# ProDoc_P1_2024-06-28.net
KiCad netlist of a schematic drawn in EasyEDA Pro
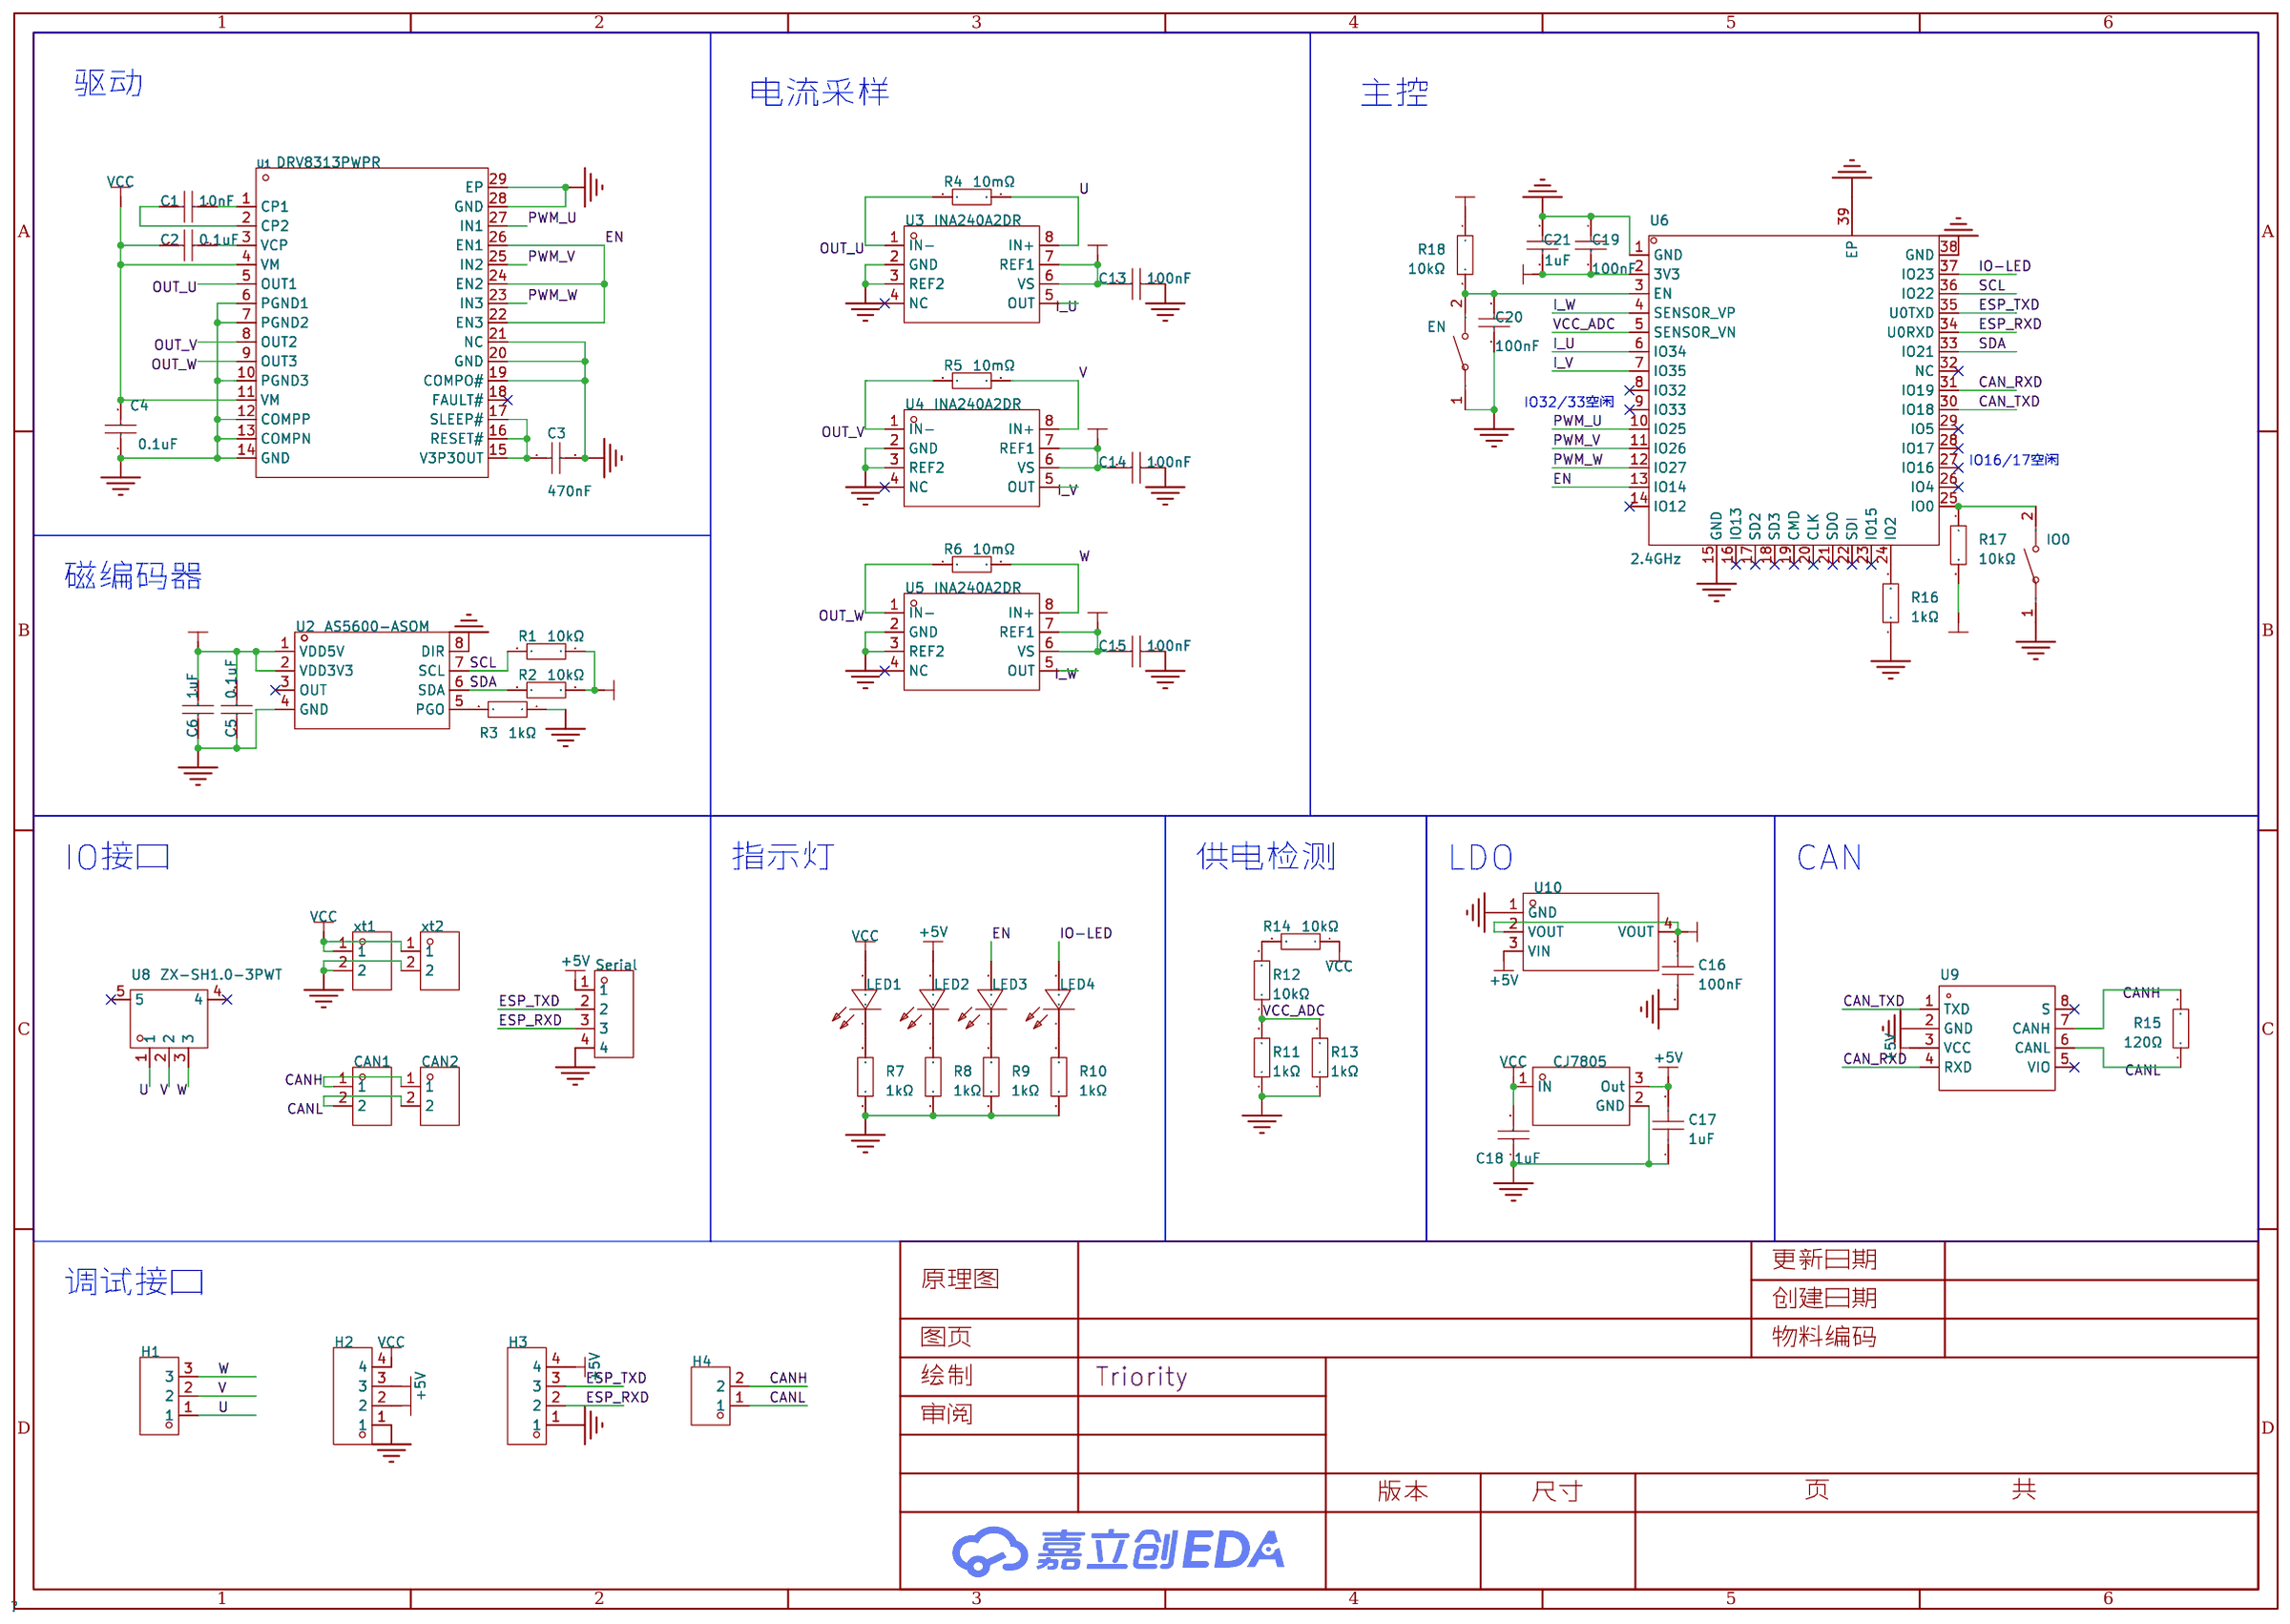
[diagram p0: schematic sheet]

(export (version "E")
  (design (tool "Eeschema 10.0.6"))
  (components
    (comp (ref "C1")
      (value "10nF")
      (footprint "easyedapro:C0603")
      (description "容值:10nF;精度:±10%;额定电压:50V;材质(温度系数):X7R;")
      (fields
        (field (name "Manufacturer Part") "CC0603KRX7R9BB103")
        (field (name "Manufacturer") "YAGEO(国巨)")
      )
      (libsource (lib "easyedapro") (part "CC0603KRX7R9BB103"))
    )
    (comp (ref "C2")
      (value "0.1uF")
      (footprint "easyedapro:C0603")
      (description "容值:100nF;精度:±10%;额定电压:50V;材质(温度系数):X7R;")
      (fields (field (name "Manufacturer Part") "0603B104K500NT") (field (name "Manufacturer") "FH(风华)"))
      (libsource (lib "easyedapro") (part "0603B104K500NT"))
    )
    (comp (ref "C3")
      (value "470nF")
      (footprint "easyedapro:C0603")
      (description "容值:470nF;精度:±10%;额定电压:25V;材质(温度系数):X7R;")
      (fields
        (field (name "Manufacturer Part") "CL10B474KA8NNNC")
        (field (name "Manufacturer") "SAMSUNG(三星)")
      )
      (libsource (lib "easyedapro") (part "CL10B474KA8NNNC"))
    )
    (comp (ref "C4")
      (value "0.1uF")
      (footprint "easyedapro:C0603")
      (description "容值:100nF;精度:±10%;额定电压:50V;材质(温度系数):X7R;")
      (fields (field (name "Manufacturer Part") "0603B104K500NT") (field (name "Manufacturer") "FH(风华)"))
      (libsource (lib "easyedapro") (part "0603B104K500NT"))
    )
    (comp (ref "C5")
      (value "0.1uF")
      (footprint "easyedapro:C0603")
      (description "容值:100nF;精度:±10%;额定电压:50V;材质(温度系数):X7R;")
      (fields (field (name "Manufacturer Part") "0603B104K500NT") (field (name "Manufacturer") "FH(风华)"))
      (libsource (lib "easyedapro") (part "0603B104K500NT"))
    )
    (comp (ref "C6")
      (value "1uF")
      (footprint "easyedapro:C0603")
      (description "容值:1uF;精度:±10%;额定电压:50V;材质(温度系数):X5R;")
      (fields
        (field (name "Manufacturer Part") "CL10A105KB8NNNC")
        (field (name "Manufacturer") "SAMSUNG(三星)")
      )
      (libsource (lib "easyedapro") (part "CL10A105KB8NNNC"))
    )
    (comp (ref "C13")
      (value "100nF")
      (footprint "easyedapro:C0603")
      (description "容值:100nF;精度:±10%;额定电压:50V;材质(温度系数):X7R;")
      (fields (field (name "Manufacturer Part") "0603B104K500NT") (field (name "Manufacturer") "FH(风华)"))
      (libsource (lib "easyedapro") (part "0603B104K500NT"))
    )
    (comp (ref "C14")
      (value "100nF")
      (footprint "easyedapro:C0603")
      (description "容值:100nF;精度:±10%;额定电压:50V;材质(温度系数):X7R;")
      (fields (field (name "Manufacturer Part") "0603B104K500NT") (field (name "Manufacturer") "FH(风华)"))
      (libsource (lib "easyedapro") (part "0603B104K500NT"))
    )
    (comp (ref "C15")
      (value "100nF")
      (footprint "easyedapro:C0603")
      (description "容值:100nF;精度:±10%;额定电压:50V;材质(温度系数):X7R;")
      (fields (field (name "Manufacturer Part") "0603B104K500NT") (field (name "Manufacturer") "FH(风华)"))
      (libsource (lib "easyedapro") (part "0603B104K500NT"))
    )
    (comp (ref "C16")
      (value "100nF")
      (footprint "easyedapro:C0603")
      (description "容值:100nF;精度:±10%;额定电压:50V;材质(温度系数):X7R;")
      (fields
        (field (name "Manufacturer Part") "CC0603KRX7R9BB104")
        (field (name "Manufacturer") "YAGEO(国巨)")
      )
      (libsource (lib "easyedapro") (part "CC0603KRX7R9BB104"))
    )
    (comp (ref "C17")
      (value "1uF")
      (footprint "easyedapro:C0603")
      (description "容值:100nF;精度:±10%;额定电压:50V;材质(温度系数):X7R;")
      (fields
        (field (name "Manufacturer Part") "CC0603KRX7R9BB104")
        (field (name "Manufacturer") "YAGEO(国巨)")
      )
      (libsource (lib "easyedapro") (part "CC0603KRX7R9BB104"))
    )
    (comp (ref "C18")
      (value "1uF")
      (footprint "easyedapro:C0603")
      (description "容值:1uF;精度:±10%;额定电压:50V;材质(温度系数):X5R;")
      (fields
        (field (name "Manufacturer Part") "CL10A105KB8NNNC")
        (field (name "Manufacturer") "SAMSUNG(三星)")
      )
      (libsource (lib "easyedapro") (part "CL10A105KB8NNNC"))
    )
    (comp (ref "C19")
      (value "100nF")
      (footprint "easyedapro:C0603")
      (description "容值:100nF;精度:±10%;额定电压:50V;材质(温度系数):X7R;")
      (fields (field (name "Manufacturer Part") "0603B104K500NT") (field (name "Manufacturer") "FH(风华)"))
      (libsource (lib "easyedapro") (part "0603B104K500NT"))
    )
    (comp (ref "C20")
      (value "100nF")
      (footprint "easyedapro:C0603")
      (description "容值:100nF;精度:±10%;额定电压:50V;材质(温度系数):X7R;")
      (fields (field (name "Manufacturer Part") "0603B104K500NT") (field (name "Manufacturer") "FH(风华)"))
      (libsource (lib "easyedapro") (part "0603B104K500NT"))
    )
    (comp (ref "C21")
      (value "1uF")
      (footprint "easyedapro:C0603")
      (description "容值:1uF;精度:±10%;额定电压:50V;材质(温度系数):X5R;")
      (fields
        (field (name "Manufacturer Part") "CL10A105KB8NNNC")
        (field (name "Manufacturer") "SAMSUNG(三星)")
      )
      (libsource (lib "easyedapro") (part "CL10A105KB8NNNC"))
    )
    (comp (ref "CAN1")
      (value "XH-2AW")
      (footprint "easyedapro:CONN-TH_XH-2AW_C2908611")
      (fields (field (name "Manufacturer") "HCTL(华灿天禄)"))
      (libsource (lib "easyedapro") (part "XH-2AW_C2908611"))
    )
    (comp (ref "CAN2")
      (value "XH-2AW")
      (footprint "easyedapro:CONN-TH_XH-2AW_C2908611")
      (fields (field (name "Manufacturer") "HCTL(华灿天禄)"))
      (libsource (lib "easyedapro") (part "XH-2AW_C2908611"))
    )
    (comp (ref "CJ7805")
      (value "CJ7805 3%")
      (footprint "easyedapro:TO-252-2_L6.6-W6.1-P4.58-LS10.1-BR-CW")
      (description "输出类型:固定;最大输入电压:35V;输出电压:5V;最大输出电流:1.5A;输出极性:正极;")
      (fields (field (name "Manufacturer") "CJ(江苏长电/长晶)"))
      (libsource (lib "easyedapro") (part "CJ7805 3%"))
    )
    (comp (ref "EN")
      (value "K2-1107ST-A4DW-06")
      (footprint "easyedapro:KEY-SMD_L6.2-W3.6-LS8.0")
      (fields (field (name "Manufacturer") "韩国韩荣"))
      (libsource (lib "easyedapro") (part "K2-1107ST-A4SW-06"))
    )
    (comp (ref "H1")
      (value "PZ254V-11-03P")
      (footprint "easyedapro:HDR-TH_3P-P2.54-V-M")
      (fields (field (name "Manufacturer") "XFCN(兴飞)"))
      (libsource (lib "easyedapro") (part "PZ254V-11-03P_C2937625"))
    )
    (comp (ref "H2")
      (value "PZ254V-11-04P")
      (footprint "easyedapro:HDR-TH_4P-P2.54-V-M")
      (fields (field (name "Manufacturer") "XFCN(兴飞)"))
      (libsource (lib "easyedapro") (part "PZ254V-11-04P_C2691448"))
    )
    (comp (ref "H3")
      (value "PZ254V-11-04P")
      (footprint "easyedapro:HDR-TH_4P-P2.54-V-M")
      (fields (field (name "Manufacturer") "XFCN(兴飞)"))
      (libsource (lib "easyedapro") (part "PZ254V-11-04P_C2691448"))
    )
    (comp (ref "H4")
      (value "PZ254V-11-02P")
      (footprint "easyedapro:HDR-TH_2P-P2.54-V-M")
      (fields (field (name "Manufacturer") "XFCN(兴飞)"))
      (libsource (lib "easyedapro") (part "PZ254V-11-02P"))
    )
    (comp (ref "IO0")
      (value "K2-1107ST-A4DW-06")
      (footprint "easyedapro:KEY-SMD_L6.2-W3.6-LS8.0")
      (fields (field (name "Manufacturer") "韩国韩荣"))
      (libsource (lib "easyedapro") (part "K2-1107ST-A4SW-06"))
    )
    (comp (ref "LED1")
      (value "KT-0603R")
      (footprint "easyedapro:LED0603-RD")
      (description "发光颜色:红色;功率:-;正向电流:-;主波长:-;二极管配置:-;透镜颜色:-;色温:-;发光角度:-;载带方式:-;工作温度:-40°C~+85°C;")
      (fields (field (name "Manufacturer") "KENTO"))
      (libsource (lib "easyedapro") (part "KT-0603R"))
    )
    (comp (ref "LED2")
      (value "KT-0603R")
      (footprint "easyedapro:LED0603-RD")
      (description "发光颜色:红色;功率:-;正向电流:-;主波长:-;二极管配置:-;透镜颜色:-;色温:-;发光角度:-;载带方式:-;工作温度:-40°C~+85°C;")
      (fields (field (name "Manufacturer") "KENTO"))
      (libsource (lib "easyedapro") (part "KT-0603R"))
    )
    (comp (ref "LED3")
      (value "KT-0603R")
      (footprint "easyedapro:LED0603-RD")
      (description "发光颜色:红色;功率:-;正向电流:-;主波长:-;二极管配置:-;透镜颜色:-;色温:-;发光角度:-;载带方式:-;工作温度:-40°C~+85°C;")
      (fields (field (name "Manufacturer") "KENTO"))
      (libsource (lib "easyedapro") (part "KT-0603R"))
    )
    (comp (ref "LED4")
      (value "KT-0603R")
      (footprint "easyedapro:LED0603-RD")
      (description "发光颜色:红色;功率:-;正向电流:-;主波长:-;二极管配置:-;透镜颜色:-;色温:-;发光角度:-;载带方式:-;工作温度:-40°C~+85°C;")
      (fields (field (name "Manufacturer") "KENTO"))
      (libsource (lib "easyedapro") (part "KT-0603R"))
    )
    (comp (ref "R1")
      (value "10kΩ")
      (footprint "easyedapro:R0603")
      (description "电阻类型:厚膜电阻;阻值:10kΩ;精度:±1%;功率:100mW;最大工作电压:75V;温度系数:±100ppm/°C;")
      (fields (field (name "Manufacturer Part") "RC0603FR-0710KL") (field (name "Manufacturer") "YAGEO(国巨)"))
      (libsource (lib "easyedapro") (part "RC0603FR-0710KL"))
    )
    (comp (ref "R2")
      (value "10kΩ")
      (footprint "easyedapro:R0603")
      (description "电阻类型:厚膜电阻;阻值:10kΩ;精度:±1%;功率:100mW;最大工作电压:75V;温度系数:±100ppm/°C;")
      (fields (field (name "Manufacturer Part") "RC0603FR-0710KL") (field (name "Manufacturer") "YAGEO(国巨)"))
      (libsource (lib "easyedapro") (part "RC0603FR-0710KL"))
    )
    (comp (ref "R3")
      (value "1kΩ")
      (footprint "easyedapro:R0603")
      (description "电阻类型:厚膜电阻;阻值:1kΩ;精度:±1%;功率:100mW;最大工作电压:75V;温度系数:±100ppm/°C;")
      (fields (field (name "Manufacturer Part") "RC0603FR-071KL") (field (name "Manufacturer") "YAGEO(国巨)"))
      (libsource (lib "easyedapro") (part "RC0603FR-071KL"))
    )
    (comp (ref "R4")
      (value "10mΩ")
      (footprint "easyedapro:R1206")
      (description "阻值:10mΩ;精度:±1%;功率:1W;温度系数:±100ppm/°C;")
      (fields (field (name "Manufacturer Part") "RLM12FTCMR010") (field (name "Manufacturer") "大毅科技"))
      (libsource (lib "easyedapro") (part "RLM12FTCMR010"))
    )
    (comp (ref "R5")
      (value "10mΩ")
      (footprint "easyedapro:R1206")
      (description "阻值:10mΩ;精度:±1%;功率:1W;温度系数:±100ppm/°C;")
      (fields (field (name "Manufacturer Part") "RLM12FTCMR010") (field (name "Manufacturer") "大毅科技"))
      (libsource (lib "easyedapro") (part "RLM12FTCMR010"))
    )
    (comp (ref "R6")
      (value "10mΩ")
      (footprint "easyedapro:R1206")
      (description "阻值:10mΩ;精度:±1%;功率:1W;温度系数:±100ppm/°C;")
      (fields (field (name "Manufacturer Part") "RLM12FTCMR010") (field (name "Manufacturer") "大毅科技"))
      (libsource (lib "easyedapro") (part "RLM12FTCMR010"))
    )
    (comp (ref "R7")
      (value "1kΩ")
      (footprint "easyedapro:R0603")
      (description "电阻类型:厚膜电阻;阻值:1kΩ;精度:±1%;功率:100mW;最大工作电压:75V;温度系数:±100ppm/°C;")
      (fields
        (field (name "Manufacturer Part") "0603WAF1001T5E")
        (field (name "Manufacturer") "UNI-ROYAL(厚声)")
      )
      (libsource (lib "easyedapro") (part "0603WAF1001T5E"))
    )
    (comp (ref "R8")
      (value "1kΩ")
      (footprint "easyedapro:R0603")
      (description "电阻类型:厚膜电阻;阻值:1kΩ;精度:±1%;功率:100mW;最大工作电压:75V;温度系数:±100ppm/°C;")
      (fields
        (field (name "Manufacturer Part") "0603WAF1001T5E")
        (field (name "Manufacturer") "UNI-ROYAL(厚声)")
      )
      (libsource (lib "easyedapro") (part "0603WAF1001T5E"))
    )
    (comp (ref "R9")
      (value "1kΩ")
      (footprint "easyedapro:R0603")
      (description "电阻类型:厚膜电阻;阻值:1kΩ;精度:±1%;功率:100mW;最大工作电压:75V;温度系数:±100ppm/°C;")
      (fields
        (field (name "Manufacturer Part") "0603WAF1001T5E")
        (field (name "Manufacturer") "UNI-ROYAL(厚声)")
      )
      (libsource (lib "easyedapro") (part "0603WAF1001T5E"))
    )
    (comp (ref "R10")
      (value "1kΩ")
      (footprint "easyedapro:R0603")
      (description "电阻类型:厚膜电阻;阻值:1kΩ;精度:±1%;功率:100mW;最大工作电压:75V;温度系数:±100ppm/°C;")
      (fields
        (field (name "Manufacturer Part") "0603WAF1001T5E")
        (field (name "Manufacturer") "UNI-ROYAL(厚声)")
      )
      (libsource (lib "easyedapro") (part "0603WAF1001T5E"))
    )
    (comp (ref "R11")
      (value "1kΩ")
      (footprint "easyedapro:R0603")
      (description "电阻类型:厚膜电阻;阻值:1kΩ;精度:±1%;功率:100mW;最大工作电压:75V;温度系数:±100ppm/°C;")
      (fields
        (field (name "Manufacturer Part") "0603WAF1001T5E")
        (field (name "Manufacturer") "UNI-ROYAL(厚声)")
      )
      (libsource (lib "easyedapro") (part "0603WAF1001T5E"))
    )
    (comp (ref "R12")
      (value "10kΩ")
      (footprint "easyedapro:R0603")
      (description "电阻类型:厚膜电阻;阻值:10kΩ;精度:±1%;功率:100mW;最大工作电压:75V;温度系数:±100ppm/°C;")
      (fields (field (name "Manufacturer Part") "RC0603FR-0710KL") (field (name "Manufacturer") "YAGEO(国巨)"))
      (libsource (lib "easyedapro") (part "RC0603FR-0710KL"))
    )
    (comp (ref "R13")
      (value "1kΩ")
      (footprint "easyedapro:R0603")
      (description "电阻类型:厚膜电阻;阻值:1kΩ;精度:±1%;功率:100mW;最大工作电压:75V;温度系数:±100ppm/°C;")
      (fields
        (field (name "Manufacturer Part") "0603WAF1001T5E")
        (field (name "Manufacturer") "UNI-ROYAL(厚声)")
      )
      (libsource (lib "easyedapro") (part "0603WAF1001T5E"))
    )
    (comp (ref "R14")
      (value "10kΩ")
      (footprint "easyedapro:R0603")
      (description "电阻类型:厚膜电阻;阻值:10kΩ;精度:±1%;功率:100mW;最大工作电压:75V;温度系数:±100ppm/°C;")
      (fields (field (name "Manufacturer Part") "RC0603FR-0710KL") (field (name "Manufacturer") "YAGEO(国巨)"))
      (libsource (lib "easyedapro") (part "RC0603FR-0710KL"))
    )
    (comp (ref "R15")
      (value "120Ω")
      (footprint "easyedapro:R0603")
      (description "电阻类型:厚膜电阻;阻值:120Ω;精度:±1%;功率:100mW;最大工作电压:75V;温度系数:±100ppm/°C;")
      (fields
        (field (name "Manufacturer Part") "0603WAF1200T5E")
        (field (name "Manufacturer") "UNI-ROYAL(厚声)")
      )
      (libsource (lib "easyedapro") (part "0603WAF1200T5E"))
    )
    (comp (ref "R16")
      (value "1kΩ")
      (footprint "easyedapro:R0603")
      (description "电阻类型:厚膜电阻;阻值:1kΩ;精度:±1%;功率:100mW;最大工作电压:75V;温度系数:±100ppm/°C;")
      (fields
        (field (name "Manufacturer Part") "0603WAF1001T5E")
        (field (name "Manufacturer") "UNI-ROYAL(厚声)")
      )
      (libsource (lib "easyedapro") (part "0603WAF1001T5E"))
    )
    (comp (ref "R17")
      (value "10kΩ")
      (footprint "easyedapro:R0603")
      (description "电阻类型:厚膜电阻;阻值:10kΩ;精度:±1%;功率:100mW;最大工作电压:75V;温度系数:±100ppm/°C;")
      (fields (field (name "Manufacturer Part") "RC0603FR-0710KL") (field (name "Manufacturer") "YAGEO(国巨)"))
      (libsource (lib "easyedapro") (part "RC0603FR-0710KL"))
    )
    (comp (ref "R18")
      (value "10kΩ")
      (footprint "easyedapro:R0603")
      (description "电阻类型:厚膜电阻;阻值:10kΩ;精度:±1%;功率:100mW;最大工作电压:75V;温度系数:±100ppm/°C;")
      (fields (field (name "Manufacturer Part") "RC0603FR-0710KL") (field (name "Manufacturer") "YAGEO(国巨)"))
      (libsource (lib "easyedapro") (part "RC0603FR-0710KL"))
    )
    (comp (ref "Serial")
      (value "XH-4AW")
      (footprint "easyedapro:CONN-TH_XH-4AW")
      (fields (field (name "Manufacturer") "HCTL(华灿天禄)"))
      (libsource (lib "easyedapro") (part "XH-4AW_C2908613"))
    )
    (comp (ref "U1")
      (value "DRV8313PWPR")
      (footprint "easyedapro:HTSSOP-28_L9.8-W4.5-P0.65-LS6.6-BL-EP")
      (description "驱动电机类型:无刷直流BLDC;电源电压:8V~60V;输出电流:-;接口:并行;")
      (fields (field (name "Manufacturer") "TI(德州仪器)"))
      (libsource (lib "easyedapro") (part "DRV8313PWPR"))
    )
    (comp (ref "U2")
      (value "AS5600-ASOM")
      (footprint "easyedapro:SOIC-8_L5.0-W4.0-P1.27-LS6.0-BL")
      (description "旋转角度范围:0°~360°;")
      (fields (field (name "Manufacturer") "ams(艾迈斯半导体)"))
      (libsource (lib "easyedapro") (part "AS5600-ASOM"))
    )
    (comp (ref "U3")
      (value "INA240A2DR")
      (footprint "easyedapro:SOIC-8_L4.9-W3.9-P1.27-LS6.0-BL")
      (description "放大器数:单路;")
      (fields (field (name "Manufacturer") "TI(德州仪器)"))
      (libsource (lib "easyedapro") (part "INA240A2DR"))
    )
    (comp (ref "U4")
      (value "INA240A2DR")
      (footprint "easyedapro:SOIC-8_L4.9-W3.9-P1.27-LS6.0-BL")
      (description "放大器数:单路;")
      (fields (field (name "Manufacturer") "TI(德州仪器)"))
      (libsource (lib "easyedapro") (part "INA240A2DR"))
    )
    (comp (ref "U5")
      (value "INA240A2DR")
      (footprint "easyedapro:SOIC-8_L4.9-W3.9-P1.27-LS6.0-BL")
      (description "放大器数:单路;")
      (fields (field (name "Manufacturer") "TI(德州仪器)"))
      (libsource (lib "easyedapro") (part "INA240A2DR"))
    )
    (comp (ref "U6")
      (value "2.4GHz")
      (footprint "easyedapro:WIRELM-SMD_ESP32-S")
      (description "核心处理器:ESP32芯片;频率:2.4GHz;天线形式:IPEX接口;发射功率:17dBm;接收灵敏度:-90dBm;")
      (fields (field (name "Manufacturer Part") "ESP32-S") (field (name "Manufacturer") "Ai-Thinker(安信可)"))
      (libsource (lib "easyedapro") (part "ESP32-S"))
    )
    (comp (ref "U8")
      (value "ZX-SH1.0-3PWT")
      (footprint "easyedapro:CONN-SMD_3P-P1.00_MEGASTAR_ZX-SH1.0-3PWT")
      (fields (field (name "Manufacturer") "Megastar(兆星)"))
      (libsource (lib "easyedapro") (part "ZX-SH1.0-3PWT"))
    )
    (comp (ref "U9")
      (value "TJA1051T/3/1J")
      (footprint "easyedapro:SOIC-8_L4.9-W3.9-P1.27-LS6.0-BL")
      (description "类型:收发器;数据速率:5Mbps;")
      (fields (field (name "Manufacturer") "NXP(恩智浦)"))
      (libsource (lib "easyedapro") (part "TJA1051T/3/1J"))
    )
    (comp (ref "U10")
      (value "AMS1117-3.3")
      (footprint "easyedapro:SOT-223-3_L6.5-W3.4-P2.30-LS7.0-BR")
      (description "输出类型:固定;最大输入电压:-;输出电压:3.3V;最大输出电流:1A;电源纹波抑制比(PSRR):72dB@(120Hz);输出极性:正极;")
      (fields (field (name "Manufacturer") "AMS"))
      (libsource (lib "easyedapro") (part "AMS1117-3.3"))
    )
    (comp (ref "xt1")
      (value "XT30U-M")
      (footprint "easyedapro:CONN-TH_XT30U-M")
      (description "类别:-;类型1:-;")
      (fields (field (name "Manufacturer") "AMASS(艾迈斯)"))
      (libsource (lib "easyedapro") (part "XT30U-M"))
    )
    (comp (ref "xt2")
      (value "XT30U-M")
      (footprint "easyedapro:CONN-TH_XT30U-M")
      (description "类别:-;类型1:-;")
      (fields (field (name "Manufacturer") "AMASS(艾迈斯)"))
      (libsource (lib "easyedapro") (part "XT30U-M"))
    )
  )
  (nets
    (net (code "1") (name "+5V") (class "Default")
      (node (ref "C17") (pin "2") (pinfunction "2_2") (pintype "unspecified"))
      (node (ref "CJ7805") (pin "3") (pinfunction "Out_3") (pintype "unspecified"))
      (node (ref "H2") (pin "3") (pinfunction "3_3") (pintype "unspecified"))
      (node (ref "H3") (pin "4") (pinfunction "4_4") (pintype "unspecified"))
      (node (ref "LED2") (pin "2") (pinfunction "A_2") (pintype "input"))
      (node (ref "Serial") (pin "1") (pinfunction "1_1") (pintype "unspecified"))
      (node (ref "U10") (pin "3") (pinfunction "VIN_3") (pintype "unspecified"))
      (node (ref "U9") (pin "3") (pinfunction "VCC_3") (pintype "input"))
    )
    (net (code "2") (name "/CANH") (class "Default")
      (node (ref "CAN1") (pin "1") (pinfunction "1_1") (pintype "unspecified"))
      (node (ref "CAN2") (pin "1") (pinfunction "1_1") (pintype "unspecified"))
      (node (ref "H4") (pin "2") (pinfunction "2_2") (pintype "unspecified"))
      (node (ref "R15") (pin "2") (pinfunction "2_2") (pintype "input"))
      (node (ref "U9") (pin "7") (pinfunction "CANH_7") (pintype "input"))
    )
    (net (code "3") (name "/CANL") (class "Default")
      (node (ref "CAN1") (pin "2") (pinfunction "2_2") (pintype "unspecified"))
      (node (ref "CAN2") (pin "2") (pinfunction "2_2") (pintype "unspecified"))
      (node (ref "H4") (pin "1") (pinfunction "1_1") (pintype "unspecified"))
      (node (ref "R15") (pin "1") (pinfunction "1_1") (pintype "input"))
      (node (ref "U9") (pin "6") (pinfunction "CANL_6") (pintype "input"))
    )
    (net (code "4") (name "/CAN_RXD") (class "Default")
      (node (ref "U6") (pin "31") (pinfunction "IO19_31") (pintype "input"))
      (node (ref "U9") (pin "4") (pinfunction "RXD_4") (pintype "input"))
    )
    (net (code "5") (name "/CAN_TXD") (class "Default")
      (node (ref "U6") (pin "30") (pinfunction "IO18_30") (pintype "input"))
      (node (ref "U9") (pin "1") (pinfunction "TXD_1") (pintype "input"))
    )
    (net (code "6") (name "/EN") (class "Default")
      (node (ref "LED3") (pin "2") (pinfunction "A_2") (pintype "input"))
      (node (ref "U1") (pin "22") (pinfunction "EN3_22") (pintype "input"))
      (node (ref "U1") (pin "24") (pinfunction "EN2_24") (pintype "input"))
      (node (ref "U1") (pin "26") (pinfunction "EN1_26") (pintype "input"))
      (node (ref "U6") (pin "13") (pinfunction "IO14_13") (pintype "input"))
    )
    (net (code "7") (name "/ESP_RXD") (class "Default")
      (node (ref "H3") (pin "2") (pinfunction "2_2") (pintype "unspecified"))
      (node (ref "Serial") (pin "3") (pinfunction "3_3") (pintype "unspecified"))
      (node (ref "U6") (pin "34") (pinfunction "U0RXD_34") (pintype "input"))
    )
    (net (code "8") (name "/ESP_TXD") (class "Default")
      (node (ref "H3") (pin "3") (pinfunction "3_3") (pintype "unspecified"))
      (node (ref "Serial") (pin "2") (pinfunction "2_2") (pintype "unspecified"))
      (node (ref "U6") (pin "35") (pinfunction "U0TXD_35") (pintype "input"))
    )
    (net (code "9") (name "/IO-LED") (class "Default")
      (node (ref "LED4") (pin "2") (pinfunction "A_2") (pintype "input"))
      (node (ref "U6") (pin "37") (pinfunction "IO23_37") (pintype "input"))
    )
    (net (code "10") (name "/I_U") (class "Default")
      (node (ref "U3") (pin "5") (pinfunction "OUT_5") (pintype "input"))
      (node (ref "U6") (pin "6") (pinfunction "IO34_6") (pintype "input"))
    )
    (net (code "11") (name "/I_V") (class "Default")
      (node (ref "U4") (pin "5") (pinfunction "OUT_5") (pintype "input"))
      (node (ref "U6") (pin "7") (pinfunction "IO35_7") (pintype "input"))
    )
    (net (code "12") (name "/I_W") (class "Default")
      (node (ref "U5") (pin "5") (pinfunction "OUT_5") (pintype "input"))
      (node (ref "U6") (pin "4") (pinfunction "SENSOR_VP_4") (pintype "input"))
    )
    (net (code "13") (name "/OUT_U") (class "Default")
      (node (ref "R4") (pin "1") (pinfunction "1_1") (pintype "input"))
      (node (ref "U1") (pin "5") (pinfunction "OUT1_5") (pintype "input"))
      (node (ref "U3") (pin "1") (pinfunction "IN-_1") (pintype "input"))
    )
    (net (code "14") (name "/OUT_V") (class "Default")
      (node (ref "R5") (pin "1") (pinfunction "1_1") (pintype "input"))
      (node (ref "U1") (pin "8") (pinfunction "OUT2_8") (pintype "input"))
      (node (ref "U4") (pin "1") (pinfunction "IN-_1") (pintype "input"))
    )
    (net (code "15") (name "/OUT_W") (class "Default")
      (node (ref "R6") (pin "1") (pinfunction "1_1") (pintype "input"))
      (node (ref "U1") (pin "9") (pinfunction "OUT3_9") (pintype "input"))
      (node (ref "U5") (pin "1") (pinfunction "IN-_1") (pintype "input"))
    )
    (net (code "16") (name "/PWM_U") (class "Default")
      (node (ref "U1") (pin "27") (pinfunction "IN1_27") (pintype "input"))
      (node (ref "U6") (pin "10") (pinfunction "IO25_10") (pintype "input"))
    )
    (net (code "17") (name "/PWM_V") (class "Default")
      (node (ref "U1") (pin "25") (pinfunction "IN2_25") (pintype "input"))
      (node (ref "U6") (pin "11") (pinfunction "IO26_11") (pintype "input"))
    )
    (net (code "18") (name "/PWM_W") (class "Default")
      (node (ref "U1") (pin "23") (pinfunction "IN3_23") (pintype "input"))
      (node (ref "U6") (pin "12") (pinfunction "IO27_12") (pintype "input"))
    )
    (net (code "19") (name "/SCL") (class "Default")
      (node (ref "R1") (pin "2") (pinfunction "2_2") (pintype "input"))
      (node (ref "U2") (pin "7") (pinfunction "SCL_7") (pintype "input"))
      (node (ref "U6") (pin "36") (pinfunction "IO22_36") (pintype "input"))
    )
    (net (code "20") (name "/SDA") (class "Default")
      (node (ref "R2") (pin "2") (pinfunction "2_2") (pintype "input"))
      (node (ref "U2") (pin "6") (pinfunction "SDA_6") (pintype "input"))
      (node (ref "U6") (pin "33") (pinfunction "IO21_33") (pintype "input"))
    )
    (net (code "21") (name "/U") (class "Default")
      (node (ref "H1") (pin "1") (pinfunction "1_1") (pintype "unspecified"))
      (node (ref "R4") (pin "2") (pinfunction "2_2") (pintype "input"))
      (node (ref "U3") (pin "8") (pinfunction "IN+_8") (pintype "input"))
      (node (ref "U8") (pin "1") (pinfunction "1_1") (pintype "unspecified"))
    )
    (net (code "22") (name "/V") (class "Default")
      (node (ref "H1") (pin "2") (pinfunction "2_2") (pintype "unspecified"))
      (node (ref "R5") (pin "2") (pinfunction "2_2") (pintype "input"))
      (node (ref "U4") (pin "8") (pinfunction "IN+_8") (pintype "input"))
      (node (ref "U8") (pin "2") (pinfunction "2_2") (pintype "unspecified"))
    )
    (net (code "23") (name "/VCC_ADC") (class "Default")
      (node (ref "R11") (pin "2") (pinfunction "2_2") (pintype "input"))
      (node (ref "R12") (pin "1") (pinfunction "1_1") (pintype "input"))
      (node (ref "R13") (pin "2") (pinfunction "2_2") (pintype "input"))
      (node (ref "U6") (pin "5") (pinfunction "SENSOR_VN_5") (pintype "input"))
    )
    (net (code "24") (name "/W") (class "Default")
      (node (ref "H1") (pin "3") (pinfunction "3_3") (pintype "unspecified"))
      (node (ref "R6") (pin "2") (pinfunction "2_2") (pintype "input"))
      (node (ref "U5") (pin "8") (pinfunction "IN+_8") (pintype "input"))
      (node (ref "U8") (pin "3") (pinfunction "3_3") (pintype "unspecified"))
    )
    (net (code "25") (name "3V3") (class "Default")
      (node (ref "C13") (pin "2") (pinfunction "2_2") (pintype "input"))
      (node (ref "C14") (pin "2") (pinfunction "2_2") (pintype "input"))
      (node (ref "C15") (pin "2") (pinfunction "2_2") (pintype "input"))
      (node (ref "C16") (pin "2") (pinfunction "2_2") (pintype "unspecified"))
      (node (ref "C19") (pin "2") (pinfunction "2_2") (pintype "input"))
      (node (ref "C21") (pin "1") (pinfunction "1_1") (pintype "input"))
      (node (ref "C5") (pin "2") (pinfunction "2_2") (pintype "input"))
      (node (ref "C6") (pin "2") (pinfunction "2_2") (pintype "input"))
      (node (ref "H2") (pin "2") (pinfunction "2_2") (pintype "unspecified"))
      (node (ref "R1") (pin "1") (pinfunction "1_1") (pintype "input"))
      (node (ref "R17") (pin "2") (pinfunction "2_2") (pintype "input"))
      (node (ref "R18") (pin "1") (pinfunction "1_1") (pintype "input"))
      (node (ref "R2") (pin "1") (pinfunction "1_1") (pintype "input"))
      (node (ref "U10") (pin "2") (pinfunction "VOUT_2") (pintype "unspecified"))
      (node (ref "U10") (pin "4") (pinfunction "VOUT_4") (pintype "unspecified"))
      (node (ref "U2") (pin "1") (pinfunction "VDD5V_1") (pintype "input"))
      (node (ref "U2") (pin "2") (pinfunction "VDD3V3_2") (pintype "input"))
      (node (ref "U3") (pin "6") (pinfunction "VS_6") (pintype "input"))
      (node (ref "U3") (pin "7") (pinfunction "REF1_7") (pintype "input"))
      (node (ref "U4") (pin "6") (pinfunction "VS_6") (pintype "input"))
      (node (ref "U4") (pin "7") (pinfunction "REF1_7") (pintype "input"))
      (node (ref "U5") (pin "6") (pinfunction "VS_6") (pintype "input"))
      (node (ref "U5") (pin "7") (pinfunction "REF1_7") (pintype "input"))
      (node (ref "U6") (pin "2") (pinfunction "3V3_2") (pintype "input"))
    )
    (net (code "26") (name "GND") (class "Default")
      (node (ref "C13") (pin "1") (pinfunction "1_1") (pintype "input"))
      (node (ref "C14") (pin "1") (pinfunction "1_1") (pintype "input"))
      (node (ref "C15") (pin "1") (pinfunction "1_1") (pintype "input"))
      (node (ref "C16") (pin "1") (pinfunction "1_1") (pintype "unspecified"))
      (node (ref "C17") (pin "1") (pinfunction "1_1") (pintype "unspecified"))
      (node (ref "C18") (pin "1") (pinfunction "1_1") (pintype "input"))
      (node (ref "C19") (pin "1") (pinfunction "1_1") (pintype "input"))
      (node (ref "C20") (pin "2") (pinfunction "2_2") (pintype "input"))
      (node (ref "C21") (pin "2") (pinfunction "2_2") (pintype "input"))
      (node (ref "C3") (pin "1") (pinfunction "1_1") (pintype "input"))
      (node (ref "C4") (pin "1") (pinfunction "1_1") (pintype "input"))
      (node (ref "C5") (pin "1") (pinfunction "1_1") (pintype "input"))
      (node (ref "C6") (pin "1") (pinfunction "1_1") (pintype "input"))
      (node (ref "CJ7805") (pin "2") (pinfunction "GND_2") (pintype "unspecified"))
      (node (ref "EN") (pin "1") (pinfunction "1_1") (pintype "input"))
      (node (ref "H2") (pin "1") (pinfunction "1_1") (pintype "unspecified"))
      (node (ref "H3") (pin "1") (pinfunction "1_1") (pintype "unspecified"))
      (node (ref "IO0") (pin "1") (pinfunction "1_1") (pintype "input"))
      (node (ref "R10") (pin "1") (pinfunction "1_1") (pintype "input"))
      (node (ref "R11") (pin "1") (pinfunction "1_1") (pintype "input"))
      (node (ref "R13") (pin "1") (pinfunction "1_1") (pintype "input"))
      (node (ref "R16") (pin "1") (pinfunction "1_1") (pintype "input"))
      (node (ref "R3") (pin "1") (pinfunction "1_1") (pintype "input"))
      (node (ref "R7") (pin "1") (pinfunction "1_1") (pintype "input"))
      (node (ref "R8") (pin "1") (pinfunction "1_1") (pintype "input"))
      (node (ref "R9") (pin "1") (pinfunction "1_1") (pintype "input"))
      (node (ref "Serial") (pin "4") (pinfunction "4_4") (pintype "unspecified"))
      (node (ref "U1") (pin "10") (pinfunction "PGND3_10") (pintype "input"))
      (node (ref "U1") (pin "12") (pinfunction "COMPP_12") (pintype "input"))
      (node (ref "U1") (pin "13") (pinfunction "COMPN_13") (pintype "input"))
      (node (ref "U1") (pin "14") (pinfunction "GND_14") (pintype "input"))
      (node (ref "U1") (pin "19") (pinfunction "COMPO#_19") (pintype "input"))
      (node (ref "U1") (pin "20") (pinfunction "GND_20") (pintype "input"))
      (node (ref "U1") (pin "21") (pinfunction "NC_21") (pintype "input"))
      (node (ref "U1") (pin "28") (pinfunction "GND_28") (pintype "input"))
      (node (ref "U1") (pin "29") (pinfunction "EP_29") (pintype "input"))
      (node (ref "U1") (pin "6") (pinfunction "PGND1_6") (pintype "input"))
      (node (ref "U1") (pin "7") (pinfunction "PGND2_7") (pintype "input"))
      (node (ref "U10") (pin "1") (pinfunction "GND_1") (pintype "unspecified"))
      (node (ref "U2") (pin "4") (pinfunction "GND_4") (pintype "input"))
      (node (ref "U2") (pin "8") (pinfunction "DIR_8") (pintype "input"))
      (node (ref "U3") (pin "2") (pinfunction "GND_2") (pintype "input"))
      (node (ref "U3") (pin "3") (pinfunction "REF2_3") (pintype "input"))
      (node (ref "U4") (pin "2") (pinfunction "GND_2") (pintype "input"))
      (node (ref "U4") (pin "3") (pinfunction "REF2_3") (pintype "input"))
      (node (ref "U5") (pin "2") (pinfunction "GND_2") (pintype "input"))
      (node (ref "U5") (pin "3") (pinfunction "REF2_3") (pintype "input"))
      (node (ref "U6") (pin "1") (pinfunction "GND_1") (pintype "input"))
      (node (ref "U6") (pin "15") (pinfunction "GND_15") (pintype "input"))
      (node (ref "U6") (pin "38") (pinfunction "GND_38") (pintype "input"))
      (node (ref "U6") (pin "39") (pinfunction "EP_39") (pintype "input"))
      (node (ref "U9") (pin "2") (pinfunction "GND_2") (pintype "input"))
      (node (ref "xt1") (pin "2") (pinfunction "2_2") (pintype "input"))
      (node (ref "xt2") (pin "2") (pinfunction "2_2") (pintype "input"))
    )
    (net (code "27") (name "Net-(LED1-K)") (class "Default")
      (node (ref "LED1") (pin "1") (pinfunction "K_1") (pintype "input"))
      (node (ref "R7") (pin "2") (pinfunction "2_2") (pintype "input"))
    )
    (net (code "28") (name "Net-(LED2-K)") (class "Default")
      (node (ref "LED2") (pin "1") (pinfunction "K_1") (pintype "input"))
      (node (ref "R8") (pin "2") (pinfunction "2_2") (pintype "input"))
    )
    (net (code "29") (name "Net-(LED3-K)") (class "Default")
      (node (ref "LED3") (pin "1") (pinfunction "K_1") (pintype "input"))
      (node (ref "R9") (pin "2") (pinfunction "2_2") (pintype "input"))
    )
    (net (code "30") (name "Net-(LED4-K)") (class "Default")
      (node (ref "LED4") (pin "1") (pinfunction "K_1") (pintype "input"))
      (node (ref "R10") (pin "2") (pinfunction "2_2") (pintype "input"))
    )
    (net (code "31") (name "Net-(R12-Pad2)") (class "Default")
      (node (ref "R12") (pin "2") (pinfunction "2_2") (pintype "input"))
      (node (ref "R14") (pin "2") (pinfunction "2_2") (pintype "input"))
    )
    (net (code "32") (name "Net-(U1-CP1)") (class "Default")
      (node (ref "C1") (pin "2") (pinfunction "2_2") (pintype "input"))
      (node (ref "U1") (pin "1") (pinfunction "CP1_1") (pintype "input"))
    )
    (net (code "33") (name "Net-(U1-CP2)") (class "Default")
      (node (ref "C1") (pin "1") (pinfunction "1_1") (pintype "input"))
      (node (ref "U1") (pin "2") (pinfunction "CP2_2") (pintype "input"))
    )
    (net (code "34") (name "Net-(U1-RESET#)") (class "Default")
      (node (ref "C3") (pin "2") (pinfunction "2_2") (pintype "input"))
      (node (ref "U1") (pin "15") (pinfunction "V3P3OUT_15") (pintype "input"))
      (node (ref "U1") (pin "16") (pinfunction "RESET#_16") (pintype "input"))
      (node (ref "U1") (pin "17") (pinfunction "SLEEP#_17") (pintype "input"))
    )
    (net (code "35") (name "Net-(U1-VCP)") (class "Default")
      (node (ref "C2") (pin "2") (pinfunction "2_2") (pintype "input"))
      (node (ref "U1") (pin "3") (pinfunction "VCP_3") (pintype "input"))
    )
    (net (code "36") (name "Net-(U2-PGO)") (class "Default")
      (node (ref "R3") (pin "2") (pinfunction "2_2") (pintype "input"))
      (node (ref "U2") (pin "5") (pinfunction "PGO_5") (pintype "input"))
    )
    (net (code "37") (name "Net-(U6-EN)") (class "Default")
      (node (ref "C20") (pin "1") (pinfunction "1_1") (pintype "input"))
      (node (ref "EN") (pin "2") (pinfunction "2_2") (pintype "input"))
      (node (ref "R18") (pin "2") (pinfunction "2_2") (pintype "input"))
      (node (ref "U6") (pin "3") (pinfunction "EN_3") (pintype "input"))
    )
    (net (code "38") (name "Net-(U6-IO0)") (class "Default")
      (node (ref "IO0") (pin "2") (pinfunction "2_2") (pintype "input"))
      (node (ref "R17") (pin "1") (pinfunction "1_1") (pintype "input"))
      (node (ref "U6") (pin "25") (pinfunction "IO0_25") (pintype "input"))
    )
    (net (code "39") (name "Net-(U6-IO2)") (class "Default")
      (node (ref "R16") (pin "2") (pinfunction "2_2") (pintype "input"))
      (node (ref "U6") (pin "24") (pinfunction "IO2_24") (pintype "input"))
    )
    (net (code "40") (name "VCC") (class "Default")
      (node (ref "C18") (pin "2") (pinfunction "2_2") (pintype "input"))
      (node (ref "C2") (pin "1") (pinfunction "1_1") (pintype "input"))
      (node (ref "C4") (pin "2") (pinfunction "2_2") (pintype "input"))
      (node (ref "CJ7805") (pin "1") (pinfunction "IN_1") (pintype "unspecified"))
      (node (ref "H2") (pin "4") (pinfunction "4_4") (pintype "unspecified"))
      (node (ref "LED1") (pin "2") (pinfunction "A_2") (pintype "input"))
      (node (ref "R14") (pin "1") (pinfunction "1_1") (pintype "input"))
      (node (ref "U1") (pin "11") (pinfunction "VM_11") (pintype "input"))
      (node (ref "U1") (pin "4") (pinfunction "VM_4") (pintype "input"))
      (node (ref "xt1") (pin "1") (pinfunction "1_1") (pintype "input"))
      (node (ref "xt2") (pin "1") (pinfunction "1_1") (pintype "input"))
    )
    (net (code "41") (name "unconnected-(U1-FAULT#-Pad18)") (class "Default")
      (node (ref "U1") (pin "18") (pinfunction "FAULT#_18") (pintype "input+no_connect"))
    )
    (net (code "42") (name "unconnected-(U2-OUT-Pad3)") (class "Default")
      (node (ref "U2") (pin "3") (pinfunction "OUT_3") (pintype "input+no_connect"))
    )
    (net (code "43") (name "unconnected-(U3-NC-Pad4)") (class "Default")
      (node (ref "U3") (pin "4") (pinfunction "NC_4") (pintype "input+no_connect"))
    )
    (net (code "44") (name "unconnected-(U4-NC-Pad4)") (class "Default")
      (node (ref "U4") (pin "4") (pinfunction "NC_4") (pintype "input+no_connect"))
    )
    (net (code "45") (name "unconnected-(U5-NC-Pad4)") (class "Default")
      (node (ref "U5") (pin "4") (pinfunction "NC_4") (pintype "input+no_connect"))
    )
    (net (code "46") (name "unconnected-(U6-CLK-Pad20)") (class "Default")
      (node (ref "U6") (pin "20") (pinfunction "CLK_20") (pintype "input+no_connect"))
    )
    (net (code "47") (name "unconnected-(U6-CMD-Pad19)") (class "Default")
      (node (ref "U6") (pin "19") (pinfunction "CMD_19") (pintype "input+no_connect"))
    )
    (net (code "48") (name "unconnected-(U6-IO4-Pad26)") (class "Default")
      (node (ref "U6") (pin "26") (pinfunction "IO4_26") (pintype "input+no_connect"))
    )
    (net (code "49") (name "unconnected-(U6-IO5-Pad29)") (class "Default")
      (node (ref "U6") (pin "29") (pinfunction "IO5_29") (pintype "input+no_connect"))
    )
    (net (code "50") (name "unconnected-(U6-IO12-Pad14)") (class "Default")
      (node (ref "U6") (pin "14") (pinfunction "IO12_14") (pintype "input+no_connect"))
    )
    (net (code "51") (name "unconnected-(U6-IO13-Pad16)") (class "Default")
      (node (ref "U6") (pin "16") (pinfunction "IO13_16") (pintype "input+no_connect"))
    )
    (net (code "52") (name "unconnected-(U6-IO15-Pad23)") (class "Default")
      (node (ref "U6") (pin "23") (pinfunction "IO15_23") (pintype "input+no_connect"))
    )
    (net (code "53") (name "unconnected-(U6-IO16-Pad27)") (class "Default")
      (node (ref "U6") (pin "27") (pinfunction "IO16_27") (pintype "input+no_connect"))
    )
    (net (code "54") (name "unconnected-(U6-IO17-Pad28)") (class "Default")
      (node (ref "U6") (pin "28") (pinfunction "IO17_28") (pintype "input+no_connect"))
    )
    (net (code "55") (name "unconnected-(U6-IO32-Pad8)") (class "Default")
      (node (ref "U6") (pin "8") (pinfunction "IO32_8") (pintype "input+no_connect"))
    )
    (net (code "56") (name "unconnected-(U6-IO33-Pad9)") (class "Default")
      (node (ref "U6") (pin "9") (pinfunction "IO33_9") (pintype "input+no_connect"))
    )
    (net (code "57") (name "unconnected-(U6-NC-Pad32)") (class "Default")
      (node (ref "U6") (pin "32") (pinfunction "NC_32") (pintype "input+no_connect"))
    )
    (net (code "58") (name "unconnected-(U6-SD2-Pad17)") (class "Default")
      (node (ref "U6") (pin "17") (pinfunction "SD2_17") (pintype "input+no_connect"))
    )
    (net (code "59") (name "unconnected-(U6-SD3-Pad18)") (class "Default")
      (node (ref "U6") (pin "18") (pinfunction "SD3_18") (pintype "input+no_connect"))
    )
    (net (code "60") (name "unconnected-(U6-SDI-Pad22)") (class "Default")
      (node (ref "U6") (pin "22") (pinfunction "SDI_22") (pintype "input+no_connect"))
    )
    (net (code "61") (name "unconnected-(U6-SDO-Pad21)") (class "Default")
      (node (ref "U6") (pin "21") (pinfunction "SDO_21") (pintype "input+no_connect"))
    )
    (net (code "62") (name "unconnected-(U8-Pad4)") (class "Default")
      (node (ref "U8") (pin "4") (pinfunction "4_4") (pintype "unspecified+no_connect"))
    )
    (net (code "63") (name "unconnected-(U8-Pad5)") (class "Default")
      (node (ref "U8") (pin "5") (pinfunction "5_5") (pintype "unspecified+no_connect"))
    )
    (net (code "64") (name "unconnected-(U9-S-Pad8)") (class "Default")
      (node (ref "U9") (pin "8") (pinfunction "S_8") (pintype "input+no_connect"))
    )
    (net (code "65") (name "unconnected-(U9-VIO-Pad5)") (class "Default")
      (node (ref "U9") (pin "5") (pinfunction "VIO_5") (pintype "input+no_connect"))
    )
  )
)
